# 7_-INPUTS.net
KiCad netlist of a schematic drawn in Altium Designer
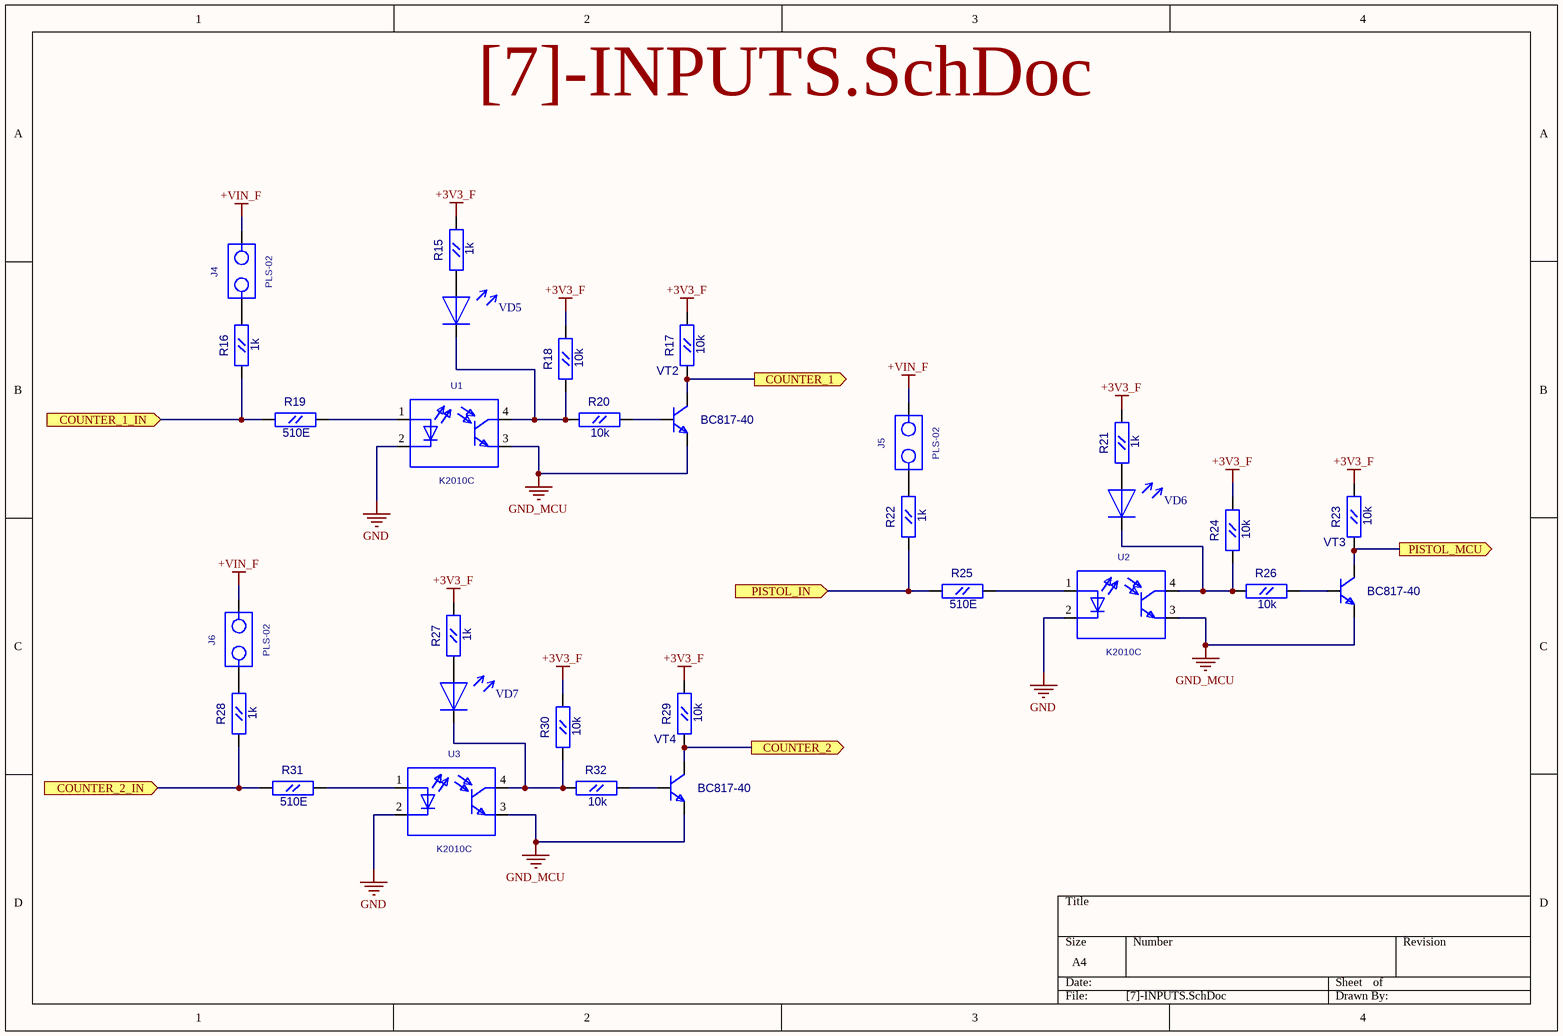
[diagram p0: [7]-INPUTS.SchDoc]

(export (version "E")
  (design (tool "Eeschema 10.0.6"))
  (components
    (comp (ref "J4") (value "PLS-02") (footprint "PLS-02") (libsource (lib "fizik_lib") (part "PLS-02")))
    (comp (ref "J5") (value "PLS-02") (footprint "PLS-02") (libsource (lib "fizik_lib") (part "PLS-02")))
    (comp (ref "J6") (value "PLS-02") (footprint "PLS-02") (libsource (lib "fizik_lib") (part "PLS-02")))
    (comp (ref "R15")
      (value "1k")
      (footprint "RC0603")
      (description "RC0603")
      (libsource (lib "fizik_lib") (part "RC0603"))
    )
    (comp (ref "R16")
      (value "1k")
      (footprint "RC0603")
      (description "RC0603")
      (libsource (lib "fizik_lib") (part "RC0603"))
    )
    (comp (ref "R17")
      (value "10k")
      (footprint "RC0603")
      (description "RC0603")
      (libsource (lib "fizik_lib") (part "RC0603"))
    )
    (comp (ref "R18")
      (value "10k")
      (footprint "RC0603")
      (description "RC0603")
      (libsource (lib "fizik_lib") (part "RC0603"))
    )
    (comp (ref "R19")
      (value "510E")
      (footprint "RC0603")
      (description "RC0603")
      (libsource (lib "fizik_lib") (part "RC0603"))
    )
    (comp (ref "R20")
      (value "10k")
      (footprint "RC0603")
      (description "RC0603")
      (libsource (lib "fizik_lib") (part "RC0603"))
    )
    (comp (ref "R21")
      (value "1k")
      (footprint "RC0603")
      (description "RC0603")
      (libsource (lib "fizik_lib") (part "RC0603"))
    )
    (comp (ref "R22")
      (value "1k")
      (footprint "RC0603")
      (description "RC0603")
      (libsource (lib "fizik_lib") (part "RC0603"))
    )
    (comp (ref "R23")
      (value "10k")
      (footprint "RC0603")
      (description "RC0603")
      (libsource (lib "fizik_lib") (part "RC0603"))
    )
    (comp (ref "R24")
      (value "10k")
      (footprint "RC0603")
      (description "RC0603")
      (libsource (lib "fizik_lib") (part "RC0603"))
    )
    (comp (ref "R25")
      (value "510E")
      (footprint "RC0603")
      (description "RC0603")
      (libsource (lib "fizik_lib") (part "RC0603"))
    )
    (comp (ref "R26")
      (value "10k")
      (footprint "RC0603")
      (description "RC0603")
      (libsource (lib "fizik_lib") (part "RC0603"))
    )
    (comp (ref "R27")
      (value "1k")
      (footprint "RC0603")
      (description "RC0603")
      (libsource (lib "fizik_lib") (part "RC0603"))
    )
    (comp (ref "R28")
      (value "1k")
      (footprint "RC0603")
      (description "RC0603")
      (libsource (lib "fizik_lib") (part "RC0603"))
    )
    (comp (ref "R29")
      (value "10k")
      (footprint "RC0603")
      (description "RC0603")
      (libsource (lib "fizik_lib") (part "RC0603"))
    )
    (comp (ref "R30")
      (value "10k")
      (footprint "RC0603")
      (description "RC0603")
      (libsource (lib "fizik_lib") (part "RC0603"))
    )
    (comp (ref "R31")
      (value "510E")
      (footprint "RC0603")
      (description "RC0603")
      (libsource (lib "fizik_lib") (part "RC0603"))
    )
    (comp (ref "R32")
      (value "10k")
      (footprint "RC0603")
      (description "RC0603")
      (libsource (lib "fizik_lib") (part "RC0603"))
    )
    (comp (ref "U1")
      (value "K2010C")
      (footprint "PC817")
      (description "K10102C")
      (libsource (lib "fizik_lib") (part "K10102C"))
    )
    (comp (ref "U2")
      (value "K2010C")
      (footprint "PC817")
      (description "K10102C")
      (libsource (lib "fizik_lib") (part "K10102C"))
    )
    (comp (ref "U3")
      (value "K2010C")
      (footprint "PC817")
      (description "K10102C")
      (libsource (lib "fizik_lib") (part "K10102C"))
    )
    (comp (ref "VD5")
      (value "LED_0805")
      (footprint "LED0805")
      (libsource (lib "fizik_lib") (part "LED_0805"))
    )
    (comp (ref "VD6")
      (value "LED_0805")
      (footprint "LED0805")
      (libsource (lib "fizik_lib") (part "LED_0805"))
    )
    (comp (ref "VD7")
      (value "LED_0805")
      (footprint "LED0805")
      (libsource (lib "fizik_lib") (part "LED_0805"))
    )
    (comp (ref "VT2")
      (value "BC817-40")
      (footprint "SOT-23(123)")
      (description "NPN 500ma transistor")
      (libsource (lib "fizik_lib") (part "BC846BLT1"))
    )
    (comp (ref "VT3")
      (value "BC817-40")
      (footprint "SOT-23(123)")
      (description "NPN 500ma transistor")
      (libsource (lib "fizik_lib") (part "BC846BLT1"))
    )
    (comp (ref "VT4")
      (value "BC817-40")
      (footprint "SOT-23(123)")
      (description "NPN 500ma transistor")
      (libsource (lib "fizik_lib") (part "BC846BLT1"))
    )
  )
  (nets
    (net (code "1") (name "+3V3_F") (class "Default")
      (node (ref "R15") (pin "2") (pinfunction "B_2") (pintype "passive"))
      (node (ref "R17") (pin "2") (pinfunction "B_2") (pintype "passive"))
      (node (ref "R18") (pin "2") (pinfunction "B_2") (pintype "passive"))
      (node (ref "R21") (pin "2") (pinfunction "B_2") (pintype "passive"))
      (node (ref "R23") (pin "2") (pinfunction "B_2") (pintype "passive"))
      (node (ref "R24") (pin "2") (pinfunction "B_2") (pintype "passive"))
      (node (ref "R27") (pin "2") (pinfunction "B_2") (pintype "passive"))
      (node (ref "R29") (pin "2") (pinfunction "B_2") (pintype "passive"))
      (node (ref "R30") (pin "2") (pinfunction "B_2") (pintype "passive"))
    )
    (net (code "2") (name "+VIN_F") (class "Default")
      (node (ref "J4") (pin "2") (pintype "passive"))
      (node (ref "J5") (pin "2") (pintype "passive"))
      (node (ref "J6") (pin "2") (pintype "passive"))
    )
    (net (code "3") (name "/COUNTER_1") (class "Default")
      (node (ref "R17") (pin "1") (pinfunction "A_1") (pintype "passive"))
      (node (ref "VT2") (pin "3") (pinfunction "C_3") (pintype "passive"))
    )
    (net (code "4") (name "/COUNTER_1_IN") (class "Default")
      (node (ref "R16") (pin "1") (pinfunction "A_1") (pintype "passive"))
      (node (ref "R19") (pin "1") (pinfunction "A_1") (pintype "passive"))
    )
    (net (code "5") (name "/COUNTER_2") (class "Default")
      (node (ref "R29") (pin "1") (pinfunction "A_1") (pintype "passive"))
      (node (ref "VT4") (pin "3") (pinfunction "C_3") (pintype "passive"))
    )
    (net (code "6") (name "/COUNTER_2_IN") (class "Default")
      (node (ref "R28") (pin "1") (pinfunction "A_1") (pintype "passive"))
      (node (ref "R31") (pin "1") (pinfunction "A_1") (pintype "passive"))
    )
    (net (code "7") (name "/PISTOL_IN") (class "Default")
      (node (ref "R22") (pin "1") (pinfunction "A_1") (pintype "passive"))
      (node (ref "R25") (pin "1") (pinfunction "A_1") (pintype "passive"))
    )
    (net (code "8") (name "/PISTOL_MCU") (class "Default")
      (node (ref "R23") (pin "1") (pinfunction "A_1") (pintype "passive"))
      (node (ref "VT3") (pin "3") (pinfunction "C_3") (pintype "passive"))
    )
    (net (code "9") (name "GND") (class "Default")
      (node (ref "U1") (pin "2") (pintype "passive"))
      (node (ref "U2") (pin "2") (pintype "passive"))
      (node (ref "U3") (pin "2") (pintype "passive"))
    )
    (net (code "10") (name "GND_MCU") (class "Default")
      (node (ref "U1") (pin "3") (pintype "passive"))
      (node (ref "U2") (pin "3") (pintype "passive"))
      (node (ref "U3") (pin "3") (pintype "passive"))
      (node (ref "VT2") (pin "2") (pinfunction "E_2") (pintype "passive"))
      (node (ref "VT3") (pin "2") (pinfunction "E_2") (pintype "passive"))
      (node (ref "VT4") (pin "2") (pinfunction "E_2") (pintype "passive"))
    )
    (net (code "11") (name "Net-(R15-A)") (class "Default")
      (node (ref "R15") (pin "1") (pinfunction "A_1") (pintype "passive"))
      (node (ref "VD5") (pin "1") (pintype "passive"))
    )
    (net (code "12") (name "Net-(R16-B)") (class "Default")
      (node (ref "J4") (pin "1") (pintype "passive"))
      (node (ref "R16") (pin "2") (pinfunction "B_2") (pintype "passive"))
    )
    (net (code "13") (name "Net-(R18-A)") (class "Default")
      (node (ref "R18") (pin "1") (pinfunction "A_1") (pintype "passive"))
      (node (ref "R20") (pin "1") (pinfunction "A_1") (pintype "passive"))
      (node (ref "U1") (pin "4") (pintype "passive"))
      (node (ref "VD5") (pin "2") (pintype "passive"))
    )
    (net (code "14") (name "Net-(R19-B)") (class "Default")
      (node (ref "R19") (pin "2") (pinfunction "B_2") (pintype "passive"))
      (node (ref "U1") (pin "1") (pintype "passive"))
    )
    (net (code "15") (name "Net-(R20-B)") (class "Default")
      (node (ref "R20") (pin "2") (pinfunction "B_2") (pintype "passive"))
      (node (ref "VT2") (pin "1") (pinfunction "B_1") (pintype "passive"))
    )
    (net (code "16") (name "Net-(R21-A)") (class "Default")
      (node (ref "R21") (pin "1") (pinfunction "A_1") (pintype "passive"))
      (node (ref "VD6") (pin "1") (pintype "passive"))
    )
    (net (code "17") (name "Net-(R22-B)") (class "Default")
      (node (ref "J5") (pin "1") (pintype "passive"))
      (node (ref "R22") (pin "2") (pinfunction "B_2") (pintype "passive"))
    )
    (net (code "18") (name "Net-(R24-A)") (class "Default")
      (node (ref "R24") (pin "1") (pinfunction "A_1") (pintype "passive"))
      (node (ref "R26") (pin "1") (pinfunction "A_1") (pintype "passive"))
      (node (ref "U2") (pin "4") (pintype "passive"))
      (node (ref "VD6") (pin "2") (pintype "passive"))
    )
    (net (code "19") (name "Net-(R25-B)") (class "Default")
      (node (ref "R25") (pin "2") (pinfunction "B_2") (pintype "passive"))
      (node (ref "U2") (pin "1") (pintype "passive"))
    )
    (net (code "20") (name "Net-(R26-B)") (class "Default")
      (node (ref "R26") (pin "2") (pinfunction "B_2") (pintype "passive"))
      (node (ref "VT3") (pin "1") (pinfunction "B_1") (pintype "passive"))
    )
    (net (code "21") (name "Net-(R27-A)") (class "Default")
      (node (ref "R27") (pin "1") (pinfunction "A_1") (pintype "passive"))
      (node (ref "VD7") (pin "1") (pintype "passive"))
    )
    (net (code "22") (name "Net-(R28-B)") (class "Default")
      (node (ref "J6") (pin "1") (pintype "passive"))
      (node (ref "R28") (pin "2") (pinfunction "B_2") (pintype "passive"))
    )
    (net (code "23") (name "Net-(R30-A)") (class "Default")
      (node (ref "R30") (pin "1") (pinfunction "A_1") (pintype "passive"))
      (node (ref "R32") (pin "1") (pinfunction "A_1") (pintype "passive"))
      (node (ref "U3") (pin "4") (pintype "passive"))
      (node (ref "VD7") (pin "2") (pintype "passive"))
    )
    (net (code "24") (name "Net-(R31-B)") (class "Default")
      (node (ref "R31") (pin "2") (pinfunction "B_2") (pintype "passive"))
      (node (ref "U3") (pin "1") (pintype "passive"))
    )
    (net (code "25") (name "Net-(R32-B)") (class "Default")
      (node (ref "R32") (pin "2") (pinfunction "B_2") (pintype "passive"))
      (node (ref "VT4") (pin "1") (pinfunction "B_1") (pintype "passive"))
    )
  )
)
